# epaper.net
KiCad netlist of a schematic drawn in EAGLE
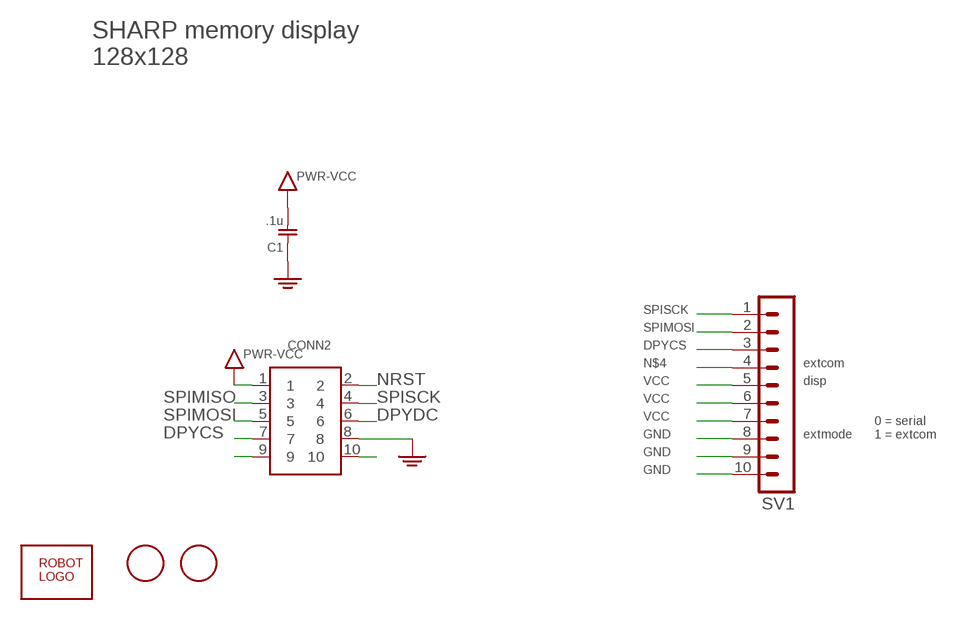
[diagram p0: schematic, sheet 1]

(export (version "E")
  (design (tool "Eeschema 10.0.6"))
  (components
    (comp (ref "C1")
      (value ".1u")
      (footprint "eagle-import:SMD0603")
      (libsource (lib "eagle-import") (part "C0603"))
    )
    (comp (ref "CONN2")
      (value "HEADER-5X2-PTH")
      (footprint "eagle-import:HEADER-5X2-PTH")
      (libsource (lib "eagle-import") (part "HEADER-5X2-PTH"))
    )
    (comp (ref "SV1")
      (value "MA10-1-M05/FFC")
      (footprint "eagle-import:M05-1X10-RA")
      (libsource (lib "eagle-import") (part "MA10-1-M05/FFC"))
    )
    (comp (ref "U$1")
      (value "ROBOTMAN-LOGO2")
      (footprint "eagle-import:ROBOTMAN-LOGO2")
      (libsource (lib "eagle-import") (part "ROBOTMAN-LOGO2"))
    )
    (comp (ref "U$2")
      (value "FIDUCIAL")
      (footprint "eagle-import:FIDUCIAL_1MM")
      (libsource (lib "eagle-import") (part "FIDUCIAL"))
    )
    (comp (ref "U$3")
      (value "FIDUCIAL")
      (footprint "eagle-import:FIDUCIAL_1MM")
      (libsource (lib "eagle-import") (part "FIDUCIAL"))
    )
  )
  (nets
    (net (code "1") (name "/DPYCS") (class "Default")
      (node (ref "CONN2") (pin "7") (pinfunction "7_7") (pintype "passive"))
      (node (ref "SV1") (pin "3") (pinfunction "3_3") (pintype "passive"))
    )
    (net (code "2") (name "/DPYDC") (class "Default")
      (node (ref "CONN2") (pin "6") (pinfunction "6_6") (pintype "passive"))
    )
    (net (code "3") (name "/N$4") (class "Default")
      (node (ref "SV1") (pin "4") (pinfunction "4_4") (pintype "passive"))
    )
    (net (code "4") (name "/NRST") (class "Default")
      (node (ref "CONN2") (pin "2") (pinfunction "2_2") (pintype "passive"))
    )
    (net (code "5") (name "/SPIMISO") (class "Default")
      (node (ref "CONN2") (pin "3") (pinfunction "3_3") (pintype "passive"))
    )
    (net (code "6") (name "/SPIMOSI") (class "Default")
      (node (ref "CONN2") (pin "5") (pinfunction "5_5") (pintype "passive"))
      (node (ref "SV1") (pin "2") (pinfunction "2_2") (pintype "passive"))
    )
    (net (code "7") (name "/SPISCK") (class "Default")
      (node (ref "CONN2") (pin "4") (pinfunction "4_4") (pintype "passive"))
      (node (ref "SV1") (pin "1") (pinfunction "1_1") (pintype "passive"))
    )
    (net (code "8") (name "PWR-GND") (class "Default")
      (node (ref "C1") (pin "1") (pinfunction "P$1_1") (pintype "passive"))
      (node (ref "CONN2") (pin "8") (pinfunction "8_8") (pintype "passive"))
      (node (ref "SV1") (pin "10") (pinfunction "10_10") (pintype "passive"))
      (node (ref "SV1") (pin "8") (pinfunction "8_8") (pintype "passive"))
      (node (ref "SV1") (pin "9") (pinfunction "9_9") (pintype "passive"))
    )
    (net (code "9") (name "PWR-VCC") (class "Default")
      (node (ref "C1") (pin "2") (pinfunction "P$2_2") (pintype "passive"))
      (node (ref "CONN2") (pin "1") (pinfunction "1_1") (pintype "passive"))
      (node (ref "SV1") (pin "5") (pinfunction "5_5") (pintype "passive"))
      (node (ref "SV1") (pin "6") (pinfunction "6_6") (pintype "passive"))
      (node (ref "SV1") (pin "7") (pinfunction "7_7") (pintype "passive"))
    )
    (net (code "10") (name "unconnected-(CONN2-Pad9)") (class "Default")
      (node (ref "CONN2") (pin "9") (pinfunction "9_9") (pintype "passive"))
    )
    (net (code "11") (name "unconnected-(CONN2-Pad10)") (class "Default")
      (node (ref "CONN2") (pin "10") (pinfunction "10_10") (pintype "passive"))
    )
  )
)
